# FPGA_Interface_Board.net
KiCad netlist of a schematic drawn in EAGLE
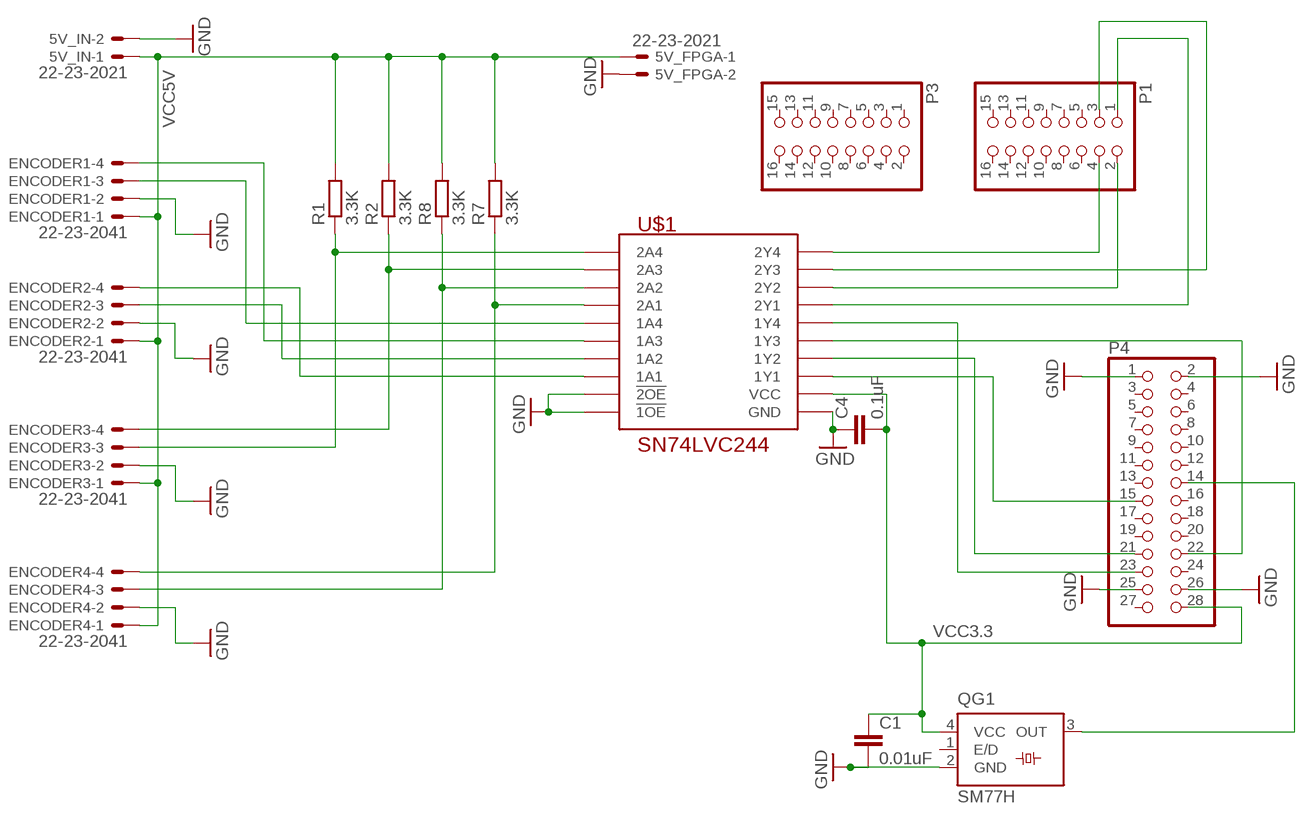
[diagram p0: schematic, sheet 1]

(export (version "E")
  (design (tool "Eeschema 10.0.6"))
  (components
    (comp (ref "5V_FPGA")
      (value "22-23-2021")
      (footprint "eagle-import:22-23-2021")
      (fields
        (field (name "MF") "MOLEX")
        (field (name "MF_1") "MOLEX")
        (field (name "MPN") "22-23-2021")
        (field (name "OC_FARNELL") "1462926")
        (field (name "OC_NEWARK") "25C3832")
      )
      (libsource (lib "eagle-import") (part "22-23-2021"))
    )
    (comp (ref "5V_IN")
      (value "22-23-2021")
      (footprint "eagle-import:22-23-2021")
      (fields (field (name "MF") "MOLEX"))
      (libsource (lib "eagle-import") (part "22-23-2021"))
    )
    (comp (ref "C1")
      (value "0.01uF")
      (footprint "eagle-import:C0603")
      (libsource (lib "eagle-import") (part "C-EUC0603"))
    )
    (comp (ref "C4")
      (value "0.1uF")
      (footprint "eagle-import:C0603")
      (libsource (lib "eagle-import") (part "C-EUC0603"))
    )
    (comp (ref "ENCODER1")
      (value "22-23-2041")
      (footprint "eagle-import:22-23-2041")
      (fields (field (name "MF") "MOLEX"))
      (libsource (lib "eagle-import") (part "22-23-2041"))
    )
    (comp (ref "ENCODER2")
      (value "22-23-2041")
      (footprint "eagle-import:22-23-2041")
      (fields (field (name "MF") "MOLEX"))
      (libsource (lib "eagle-import") (part "22-23-2041"))
    )
    (comp (ref "ENCODER3")
      (value "22-23-2041")
      (footprint "eagle-import:22-23-2041")
      (fields (field (name "MF") "MOLEX"))
      (libsource (lib "eagle-import") (part "22-23-2041"))
    )
    (comp (ref "ENCODER4")
      (value "22-23-2041")
      (footprint "eagle-import:22-23-2041")
      (fields (field (name "MF") "MOLEX"))
      (libsource (lib "eagle-import") (part "22-23-2041"))
    )
    (comp (ref "P1")
      (value "PINHD-2X8")
      (footprint "eagle-import:2X08")
      (libsource (lib "eagle-import") (part "PINHD-2X8"))
    )
    (comp (ref "P3")
      (value "PINHD-2X8")
      (footprint "eagle-import:2X08")
      (libsource (lib "eagle-import") (part "PINHD-2X8"))
    )
    (comp (ref "P4")
      (value "PINHD-2X14")
      (footprint "eagle-import:2X14")
      (libsource (lib "eagle-import") (part "PINHD-2X14"))
    )
    (comp (ref "QG1")
      (value "SM77H")
      (footprint "eagle-import:SM77H")
      (libsource (lib "eagle-import") (part "SM77H"))
    )
    (comp (ref "R1")
      (value "3.3K")
      (footprint "eagle-import:R0603")
      (libsource (lib "eagle-import") (part "R-EU_R0603"))
    )
    (comp (ref "R2")
      (value "3.3K")
      (footprint "eagle-import:R0603")
      (libsource (lib "eagle-import") (part "R-EU_R0603"))
    )
    (comp (ref "R7")
      (value "3.3K")
      (footprint "eagle-import:R0603")
      (libsource (lib "eagle-import") (part "R-EU_R0603"))
    )
    (comp (ref "R8")
      (value "3.3K")
      (footprint "eagle-import:R0603")
      (libsource (lib "eagle-import") (part "R-EU_R0603"))
    )
    (comp (ref "U$1")
      (value "SN74LVC244")
      (footprint "eagle-import:TSSOP-20-0.65MM")
      (libsource (lib "eagle-import") (part "SN74LVC244"))
    )
  )
  (nets
    (net (code "1") (name "/VCC3.3") (class "Default")
      (node (ref "C1") (pin "1") (pinfunction "1_1") (pintype "passive"))
      (node (ref "C4") (pin "2") (pinfunction "2_2") (pintype "passive"))
      (node (ref "P4") (pin "28") (pinfunction "28_28") (pintype "passive"))
      (node (ref "QG1") (pin "4") (pinfunction "VCC_4") (pintype "power_in"))
      (node (ref "U$1") (pin "P$20") (pinfunction "VCC_P$20") (pintype "bidirectional"))
    )
    (net (code "2") (name "/VCC5V") (class "Default")
      (node (ref "5V_FPGA") (pin "1") (pinfunction "S_1") (pintype "passive"))
      (node (ref "5V_IN") (pin "1") (pinfunction "S_1") (pintype "passive"))
      (node (ref "ENCODER1") (pin "1") (pinfunction "S_1") (pintype "passive"))
      (node (ref "ENCODER2") (pin "1") (pinfunction "S_1") (pintype "passive"))
      (node (ref "ENCODER3") (pin "1") (pinfunction "S_1") (pintype "passive"))
      (node (ref "ENCODER4") (pin "1") (pinfunction "S_1") (pintype "passive"))
      (node (ref "R1") (pin "2") (pinfunction "2_2") (pintype "passive"))
      (node (ref "R2") (pin "2") (pinfunction "2_2") (pintype "passive"))
      (node (ref "R7") (pin "2") (pinfunction "2_2") (pintype "passive"))
      (node (ref "R8") (pin "2") (pinfunction "2_2") (pintype "passive"))
    )
    (net (code "3") (name "GND") (class "Default")
      (node (ref "5V_FPGA") (pin "2") (pinfunction "S_2") (pintype "passive"))
      (node (ref "5V_IN") (pin "2") (pinfunction "S_2") (pintype "passive"))
      (node (ref "C1") (pin "2") (pinfunction "2_2") (pintype "passive"))
      (node (ref "C4") (pin "1") (pinfunction "1_1") (pintype "passive"))
      (node (ref "ENCODER1") (pin "2") (pinfunction "S_2") (pintype "passive"))
      (node (ref "ENCODER2") (pin "2") (pinfunction "S_2") (pintype "passive"))
      (node (ref "ENCODER3") (pin "2") (pinfunction "S_2") (pintype "passive"))
      (node (ref "ENCODER4") (pin "2") (pinfunction "S_2") (pintype "passive"))
      (node (ref "P4") (pin "1") (pinfunction "1_1") (pintype "passive"))
      (node (ref "P4") (pin "2") (pinfunction "2_2") (pintype "passive"))
      (node (ref "P4") (pin "25") (pinfunction "25_25") (pintype "passive"))
      (node (ref "P4") (pin "26") (pinfunction "26_26") (pintype "passive"))
      (node (ref "QG1") (pin "2") (pinfunction "GND_2") (pintype "power_in"))
      (node (ref "U$1") (pin "P$1") (pinfunction "~{1OE}_P$1") (pintype "bidirectional"))
      (node (ref "U$1") (pin "P$10") (pinfunction "GND_P$10") (pintype "bidirectional"))
      (node (ref "U$1") (pin "P$19") (pinfunction "~{2OE}_P$19") (pintype "bidirectional"))
    )
    (net (code "4") (name "Net-(ENCODER1C-S)") (class "Default")
      (node (ref "ENCODER1") (pin "3") (pinfunction "S_3") (pintype "passive"))
      (node (ref "U$1") (pin "P$8") (pinfunction "1A4_P$8") (pintype "bidirectional"))
    )
    (net (code "5") (name "Net-(ENCODER1D-S)") (class "Default")
      (node (ref "ENCODER1") (pin "4") (pinfunction "S_4") (pintype "passive"))
      (node (ref "U$1") (pin "P$6") (pinfunction "1A3_P$6") (pintype "bidirectional"))
    )
    (net (code "6") (name "Net-(ENCODER2C-S)") (class "Default")
      (node (ref "ENCODER2") (pin "3") (pinfunction "S_3") (pintype "passive"))
      (node (ref "U$1") (pin "P$4") (pinfunction "1A2_P$4") (pintype "bidirectional"))
    )
    (net (code "7") (name "Net-(ENCODER2D-S)") (class "Default")
      (node (ref "ENCODER2") (pin "4") (pinfunction "S_4") (pintype "passive"))
      (node (ref "U$1") (pin "P$2") (pinfunction "1A1_P$2") (pintype "bidirectional"))
    )
    (net (code "8") (name "Net-(ENCODER3C-S)") (class "Default")
      (node (ref "ENCODER3") (pin "3") (pinfunction "S_3") (pintype "passive"))
      (node (ref "R1") (pin "1") (pinfunction "1_1") (pintype "passive"))
      (node (ref "U$1") (pin "P$17") (pinfunction "2A4_P$17") (pintype "bidirectional"))
    )
    (net (code "9") (name "Net-(ENCODER3D-S)") (class "Default")
      (node (ref "ENCODER3") (pin "4") (pinfunction "S_4") (pintype "passive"))
      (node (ref "R2") (pin "1") (pinfunction "1_1") (pintype "passive"))
      (node (ref "U$1") (pin "P$15") (pinfunction "2A3_P$15") (pintype "bidirectional"))
    )
    (net (code "10") (name "Net-(ENCODER4C-S)") (class "Default")
      (node (ref "ENCODER4") (pin "3") (pinfunction "S_3") (pintype "passive"))
      (node (ref "R8") (pin "1") (pinfunction "1_1") (pintype "passive"))
      (node (ref "U$1") (pin "P$13") (pinfunction "2A2_P$13") (pintype "bidirectional"))
    )
    (net (code "11") (name "Net-(ENCODER4D-S)") (class "Default")
      (node (ref "ENCODER4") (pin "4") (pinfunction "S_4") (pintype "passive"))
      (node (ref "R7") (pin "1") (pinfunction "1_1") (pintype "passive"))
      (node (ref "U$1") (pin "P$11") (pinfunction "2A1_P$11") (pintype "bidirectional"))
    )
    (net (code "12") (name "Net-(QG1-OUT)") (class "Default")
      (node (ref "P4") (pin "14") (pinfunction "14_14") (pintype "passive"))
      (node (ref "QG1") (pin "3") (pinfunction "OUT_3") (pintype "output"))
    )
    (net (code "13") (name "Net-(U$1-1Y1)") (class "Default")
      (node (ref "P4") (pin "15") (pinfunction "15_15") (pintype "passive"))
      (node (ref "U$1") (pin "P$18") (pinfunction "1Y1_P$18") (pintype "bidirectional"))
    )
    (net (code "14") (name "Net-(U$1-1Y2)") (class "Default")
      (node (ref "P4") (pin "21") (pinfunction "21_21") (pintype "passive"))
      (node (ref "U$1") (pin "P$16") (pinfunction "1Y2_P$16") (pintype "bidirectional"))
    )
    (net (code "15") (name "Net-(U$1-1Y3)") (class "Default")
      (node (ref "P4") (pin "22") (pinfunction "22_22") (pintype "passive"))
      (node (ref "U$1") (pin "P$14") (pinfunction "1Y3_P$14") (pintype "bidirectional"))
    )
    (net (code "16") (name "Net-(U$1-1Y4)") (class "Default")
      (node (ref "P4") (pin "23") (pinfunction "23_23") (pintype "passive"))
      (node (ref "U$1") (pin "P$12") (pinfunction "1Y4_P$12") (pintype "bidirectional"))
    )
    (net (code "17") (name "Net-(U$1-2Y1)") (class "Default")
      (node (ref "P1") (pin "1") (pinfunction "1_1") (pintype "passive"))
      (node (ref "U$1") (pin "P$9") (pinfunction "2Y1_P$9") (pintype "bidirectional"))
    )
    (net (code "18") (name "Net-(U$1-2Y2)") (class "Default")
      (node (ref "P1") (pin "2") (pinfunction "2_2") (pintype "passive"))
      (node (ref "U$1") (pin "P$7") (pinfunction "2Y2_P$7") (pintype "bidirectional"))
    )
    (net (code "19") (name "Net-(U$1-2Y3)") (class "Default")
      (node (ref "P1") (pin "3") (pinfunction "3_3") (pintype "passive"))
      (node (ref "U$1") (pin "P$5") (pinfunction "2Y3_P$5") (pintype "bidirectional"))
    )
    (net (code "20") (name "Net-(U$1-2Y4)") (class "Default")
      (node (ref "P1") (pin "4") (pinfunction "4_4") (pintype "passive"))
      (node (ref "U$1") (pin "P$3") (pinfunction "2Y4_P$3") (pintype "bidirectional"))
    )
    (net (code "21") (name "unconnected-(P1-Pad5)") (class "Default")
      (node (ref "P1") (pin "5") (pinfunction "5_5") (pintype "passive"))
    )
    (net (code "22") (name "unconnected-(P1-Pad6)") (class "Default")
      (node (ref "P1") (pin "6") (pinfunction "6_6") (pintype "passive"))
    )
    (net (code "23") (name "unconnected-(P1-Pad7)") (class "Default")
      (node (ref "P1") (pin "7") (pinfunction "7_7") (pintype "passive"))
    )
    (net (code "24") (name "unconnected-(P1-Pad8)") (class "Default")
      (node (ref "P1") (pin "8") (pinfunction "8_8") (pintype "passive"))
    )
    (net (code "25") (name "unconnected-(P1-Pad9)") (class "Default")
      (node (ref "P1") (pin "9") (pinfunction "9_9") (pintype "passive"))
    )
    (net (code "26") (name "unconnected-(P1-Pad10)") (class "Default")
      (node (ref "P1") (pin "10") (pinfunction "10_10") (pintype "passive"))
    )
    (net (code "27") (name "unconnected-(P1-Pad11)") (class "Default")
      (node (ref "P1") (pin "11") (pinfunction "11_11") (pintype "passive"))
    )
    (net (code "28") (name "unconnected-(P1-Pad12)") (class "Default")
      (node (ref "P1") (pin "12") (pinfunction "12_12") (pintype "passive"))
    )
    (net (code "29") (name "unconnected-(P1-Pad13)") (class "Default")
      (node (ref "P1") (pin "13") (pinfunction "13_13") (pintype "passive"))
    )
    (net (code "30") (name "unconnected-(P1-Pad14)") (class "Default")
      (node (ref "P1") (pin "14") (pinfunction "14_14") (pintype "passive"))
    )
    (net (code "31") (name "unconnected-(P1-Pad15)") (class "Default")
      (node (ref "P1") (pin "15") (pinfunction "15_15") (pintype "passive"))
    )
    (net (code "32") (name "unconnected-(P1-Pad16)") (class "Default")
      (node (ref "P1") (pin "16") (pinfunction "16_16") (pintype "passive"))
    )
    (net (code "33") (name "unconnected-(P3-Pad1)") (class "Default")
      (node (ref "P3") (pin "1") (pinfunction "1_1") (pintype "passive"))
    )
    (net (code "34") (name "unconnected-(P3-Pad2)") (class "Default")
      (node (ref "P3") (pin "2") (pinfunction "2_2") (pintype "passive"))
    )
    (net (code "35") (name "unconnected-(P3-Pad3)") (class "Default")
      (node (ref "P3") (pin "3") (pinfunction "3_3") (pintype "passive"))
    )
    (net (code "36") (name "unconnected-(P3-Pad4)") (class "Default")
      (node (ref "P3") (pin "4") (pinfunction "4_4") (pintype "passive"))
    )
    (net (code "37") (name "unconnected-(P3-Pad5)") (class "Default")
      (node (ref "P3") (pin "5") (pinfunction "5_5") (pintype "passive"))
    )
    (net (code "38") (name "unconnected-(P3-Pad6)") (class "Default")
      (node (ref "P3") (pin "6") (pinfunction "6_6") (pintype "passive"))
    )
    (net (code "39") (name "unconnected-(P3-Pad7)") (class "Default")
      (node (ref "P3") (pin "7") (pinfunction "7_7") (pintype "passive"))
    )
    (net (code "40") (name "unconnected-(P3-Pad8)") (class "Default")
      (node (ref "P3") (pin "8") (pinfunction "8_8") (pintype "passive"))
    )
    (net (code "41") (name "unconnected-(P3-Pad9)") (class "Default")
      (node (ref "P3") (pin "9") (pinfunction "9_9") (pintype "passive"))
    )
    (net (code "42") (name "unconnected-(P3-Pad10)") (class "Default")
      (node (ref "P3") (pin "10") (pinfunction "10_10") (pintype "passive"))
    )
    (net (code "43") (name "unconnected-(P3-Pad11)") (class "Default")
      (node (ref "P3") (pin "11") (pinfunction "11_11") (pintype "passive"))
    )
    (net (code "44") (name "unconnected-(P3-Pad12)") (class "Default")
      (node (ref "P3") (pin "12") (pinfunction "12_12") (pintype "passive"))
    )
    (net (code "45") (name "unconnected-(P3-Pad13)") (class "Default")
      (node (ref "P3") (pin "13") (pinfunction "13_13") (pintype "passive"))
    )
    (net (code "46") (name "unconnected-(P3-Pad14)") (class "Default")
      (node (ref "P3") (pin "14") (pinfunction "14_14") (pintype "passive"))
    )
    (net (code "47") (name "unconnected-(P3-Pad15)") (class "Default")
      (node (ref "P3") (pin "15") (pinfunction "15_15") (pintype "passive"))
    )
    (net (code "48") (name "unconnected-(P3-Pad16)") (class "Default")
      (node (ref "P3") (pin "16") (pinfunction "16_16") (pintype "passive"))
    )
    (net (code "49") (name "unconnected-(P4-Pad3)") (class "Default")
      (node (ref "P4") (pin "3") (pinfunction "3_3") (pintype "passive"))
    )
    (net (code "50") (name "unconnected-(P4-Pad4)") (class "Default")
      (node (ref "P4") (pin "4") (pinfunction "4_4") (pintype "passive"))
    )
    (net (code "51") (name "unconnected-(P4-Pad5)") (class "Default")
      (node (ref "P4") (pin "5") (pinfunction "5_5") (pintype "passive"))
    )
    (net (code "52") (name "unconnected-(P4-Pad6)") (class "Default")
      (node (ref "P4") (pin "6") (pinfunction "6_6") (pintype "passive"))
    )
    (net (code "53") (name "unconnected-(P4-Pad7)") (class "Default")
      (node (ref "P4") (pin "7") (pinfunction "7_7") (pintype "passive"))
    )
    (net (code "54") (name "unconnected-(P4-Pad8)") (class "Default")
      (node (ref "P4") (pin "8") (pinfunction "8_8") (pintype "passive"))
    )
    (net (code "55") (name "unconnected-(P4-Pad9)") (class "Default")
      (node (ref "P4") (pin "9") (pinfunction "9_9") (pintype "passive"))
    )
    (net (code "56") (name "unconnected-(P4-Pad10)") (class "Default")
      (node (ref "P4") (pin "10") (pinfunction "10_10") (pintype "passive"))
    )
    (net (code "57") (name "unconnected-(P4-Pad11)") (class "Default")
      (node (ref "P4") (pin "11") (pinfunction "11_11") (pintype "passive"))
    )
    (net (code "58") (name "unconnected-(P4-Pad12)") (class "Default")
      (node (ref "P4") (pin "12") (pinfunction "12_12") (pintype "passive"))
    )
    (net (code "59") (name "unconnected-(P4-Pad13)") (class "Default")
      (node (ref "P4") (pin "13") (pinfunction "13_13") (pintype "passive"))
    )
    (net (code "60") (name "unconnected-(P4-Pad16)") (class "Default")
      (node (ref "P4") (pin "16") (pinfunction "16_16") (pintype "passive"))
    )
    (net (code "61") (name "unconnected-(P4-Pad17)") (class "Default")
      (node (ref "P4") (pin "17") (pinfunction "17_17") (pintype "passive"))
    )
    (net (code "62") (name "unconnected-(P4-Pad18)") (class "Default")
      (node (ref "P4") (pin "18") (pinfunction "18_18") (pintype "passive"))
    )
    (net (code "63") (name "unconnected-(P4-Pad19)") (class "Default")
      (node (ref "P4") (pin "19") (pinfunction "19_19") (pintype "passive"))
    )
    (net (code "64") (name "unconnected-(P4-Pad20)") (class "Default")
      (node (ref "P4") (pin "20") (pinfunction "20_20") (pintype "passive"))
    )
    (net (code "65") (name "unconnected-(P4-Pad24)") (class "Default")
      (node (ref "P4") (pin "24") (pinfunction "24_24") (pintype "passive"))
    )
    (net (code "66") (name "unconnected-(P4-Pad27)") (class "Default")
      (node (ref "P4") (pin "27") (pinfunction "27_27") (pintype "passive"))
    )
    (net (code "67") (name "unconnected-(QG1-E{slash}D-Pad1)") (class "Default")
      (node (ref "QG1") (pin "1") (pinfunction "E/D_1") (pintype "input"))
    )
  )
)
